# main.net
KiCad netlist of a schematic drawn in EAGLE
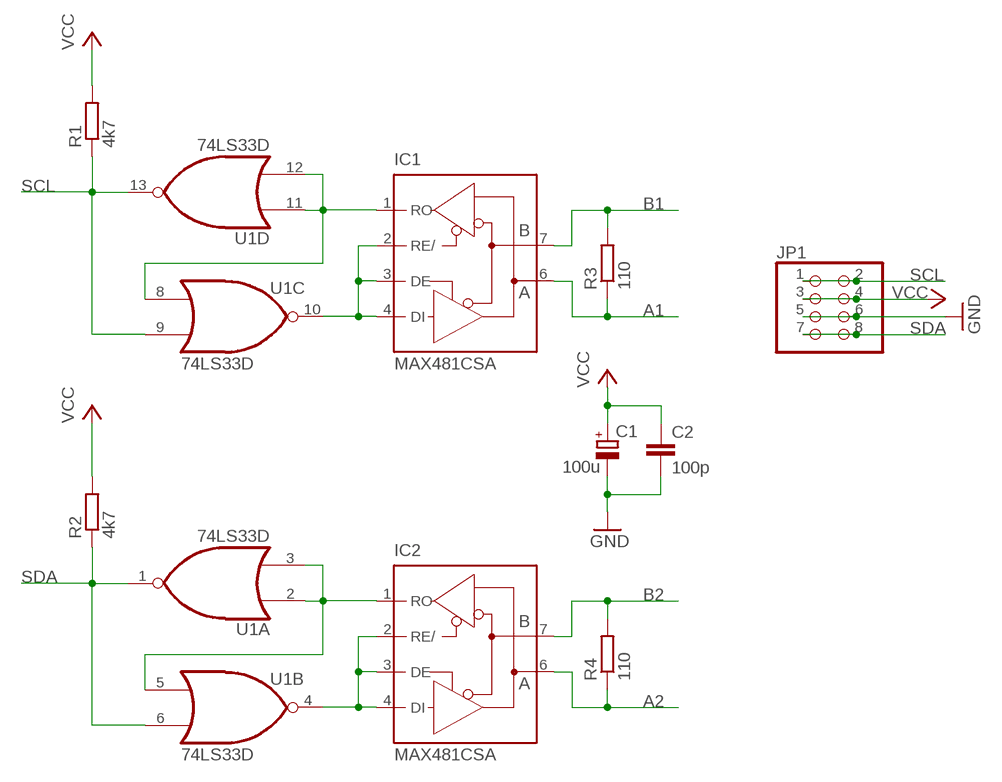
[diagram p0: schematic, sheet 1]

(export (version "E")
  (design (tool "Eeschema 10.0.6"))
  (components
    (comp (ref "C1")
      (value "100u")
      (footprint "eagle-import:E2-4")
      (libsource (lib "eagle-import") (part "CPOL-EUE2-4"))
    )
    (comp (ref "C2")
      (value "100p")
      (footprint "eagle-import:C025-024X044")
      (libsource (lib "eagle-import") (part "C-EU025-024X044"))
    )
    (comp (ref "IC1")
      (value "MAX481CSA")
      (footprint "eagle-import:SO08")
      (libsource (lib "eagle-import") (part "MAX481CSA"))
    )
    (comp (ref "IC2")
      (value "MAX481CSA")
      (footprint "eagle-import:SO08")
      (libsource (lib "eagle-import") (part "MAX481CSA"))
    )
    (comp (ref "JP1")
      (value "PINHD-2X4")
      (footprint "eagle-import:2X04")
      (libsource (lib "eagle-import") (part "PINHD-2X4"))
    )
    (comp (ref "R1")
      (value "4k7")
      (footprint "eagle-import:R0805")
      (libsource (lib "eagle-import") (part "R-EU_R0805"))
    )
    (comp (ref "R2")
      (value "4k7")
      (footprint "eagle-import:R0805")
      (libsource (lib "eagle-import") (part "R-EU_R0805"))
    )
    (comp (ref "R3")
      (value "110")
      (footprint "eagle-import:R0805")
      (libsource (lib "eagle-import") (part "R-EU_R0805"))
    )
    (comp (ref "R4")
      (value "110")
      (footprint "eagle-import:R0805")
      (libsource (lib "eagle-import") (part "R-EU_R0805"))
    )
    (comp (ref "U1")
      (value "74LS33D")
      (footprint "eagle-import:SO14")
      (libsource (lib "eagle-import") (part "7433DLS"))
    )
  )
  (nets
    (net (code "1") (name "/A1") (class "Default")
      (node (ref "IC1") (pin "6") (pinfunction "A_6") (pintype "passive"))
      (node (ref "R3") (pin "1") (pinfunction "1_1") (pintype "passive"))
    )
    (net (code "2") (name "/A2") (class "Default")
      (node (ref "IC2") (pin "6") (pinfunction "A_6") (pintype "passive"))
      (node (ref "R4") (pin "1") (pinfunction "1_1") (pintype "passive"))
    )
    (net (code "3") (name "/B1") (class "Default")
      (node (ref "IC1") (pin "7") (pinfunction "B_7") (pintype "passive"))
      (node (ref "R3") (pin "2") (pinfunction "2_2") (pintype "passive"))
    )
    (net (code "4") (name "/B2") (class "Default")
      (node (ref "IC2") (pin "7") (pinfunction "B_7") (pintype "passive"))
      (node (ref "R4") (pin "2") (pinfunction "2_2") (pintype "passive"))
    )
    (net (code "5") (name "/SCL") (class "Default")
      (node (ref "JP1") (pin "1") (pinfunction "1_1") (pintype "passive"))
      (node (ref "JP1") (pin "2") (pinfunction "2_2") (pintype "passive"))
      (node (ref "R1") (pin "1") (pinfunction "1_1") (pintype "passive"))
      (node (ref "U1") (pin "13") (pinfunction "O_13") (pintype "output"))
      (node (ref "U1") (pin "9") (pinfunction "I1_9") (pintype "input"))
    )
    (net (code "6") (name "/SDA") (class "Default")
      (node (ref "JP1") (pin "7") (pinfunction "7_7") (pintype "passive"))
      (node (ref "JP1") (pin "8") (pinfunction "8_8") (pintype "passive"))
      (node (ref "R2") (pin "1") (pinfunction "1_1") (pintype "passive"))
      (node (ref "U1") (pin "1") (pinfunction "O_1") (pintype "output"))
      (node (ref "U1") (pin "6") (pinfunction "I1_6") (pintype "input"))
    )
    (net (code "7") (name "GND") (class "Default")
      (node (ref "C1") (pin "-") (pinfunction "-_-") (pintype "passive"))
      (node (ref "C2") (pin "2") (pinfunction "2_2") (pintype "passive"))
      (node (ref "JP1") (pin "5") (pinfunction "5_5") (pintype "passive"))
      (node (ref "JP1") (pin "6") (pinfunction "6_6") (pintype "passive"))
    )
    (net (code "8") (name "Net-(IC1A-DE)") (class "Default")
      (node (ref "IC1") (pin "2") (pinfunction "RE/_2") (pintype "input"))
      (node (ref "IC1") (pin "3") (pinfunction "DE_3") (pintype "input"))
      (node (ref "IC1") (pin "4") (pinfunction "DI_4") (pintype "input"))
      (node (ref "U1") (pin "10") (pinfunction "O_10") (pintype "output"))
    )
    (net (code "9") (name "Net-(IC1A-RO)") (class "Default")
      (node (ref "IC1") (pin "1") (pinfunction "RO_1") (pintype "output"))
      (node (ref "U1") (pin "11") (pinfunction "I0_11") (pintype "input"))
      (node (ref "U1") (pin "12") (pinfunction "I1_12") (pintype "input"))
      (node (ref "U1") (pin "8") (pinfunction "I0_8") (pintype "input"))
    )
    (net (code "10") (name "Net-(IC2A-DE)") (class "Default")
      (node (ref "IC2") (pin "2") (pinfunction "RE/_2") (pintype "input"))
      (node (ref "IC2") (pin "3") (pinfunction "DE_3") (pintype "input"))
      (node (ref "IC2") (pin "4") (pinfunction "DI_4") (pintype "input"))
      (node (ref "U1") (pin "4") (pinfunction "O_4") (pintype "output"))
    )
    (net (code "11") (name "Net-(IC2A-RO)") (class "Default")
      (node (ref "IC2") (pin "1") (pinfunction "RO_1") (pintype "output"))
      (node (ref "U1") (pin "2") (pinfunction "I0_2") (pintype "input"))
      (node (ref "U1") (pin "3") (pinfunction "I1_3") (pintype "input"))
      (node (ref "U1") (pin "5") (pinfunction "I0_5") (pintype "input"))
    )
    (net (code "12") (name "VCC") (class "Default")
      (node (ref "C1") (pin "+") (pinfunction "+_+") (pintype "passive"))
      (node (ref "C2") (pin "1") (pinfunction "1_1") (pintype "passive"))
      (node (ref "JP1") (pin "3") (pinfunction "3_3") (pintype "passive"))
      (node (ref "JP1") (pin "4") (pinfunction "4_4") (pintype "passive"))
      (node (ref "R1") (pin "2") (pinfunction "2_2") (pintype "passive"))
      (node (ref "R2") (pin "2") (pinfunction "2_2") (pintype "passive"))
    )
  )
)
